# Brain_V0_1.net
KiCad netlist of a schematic drawn in EAGLE
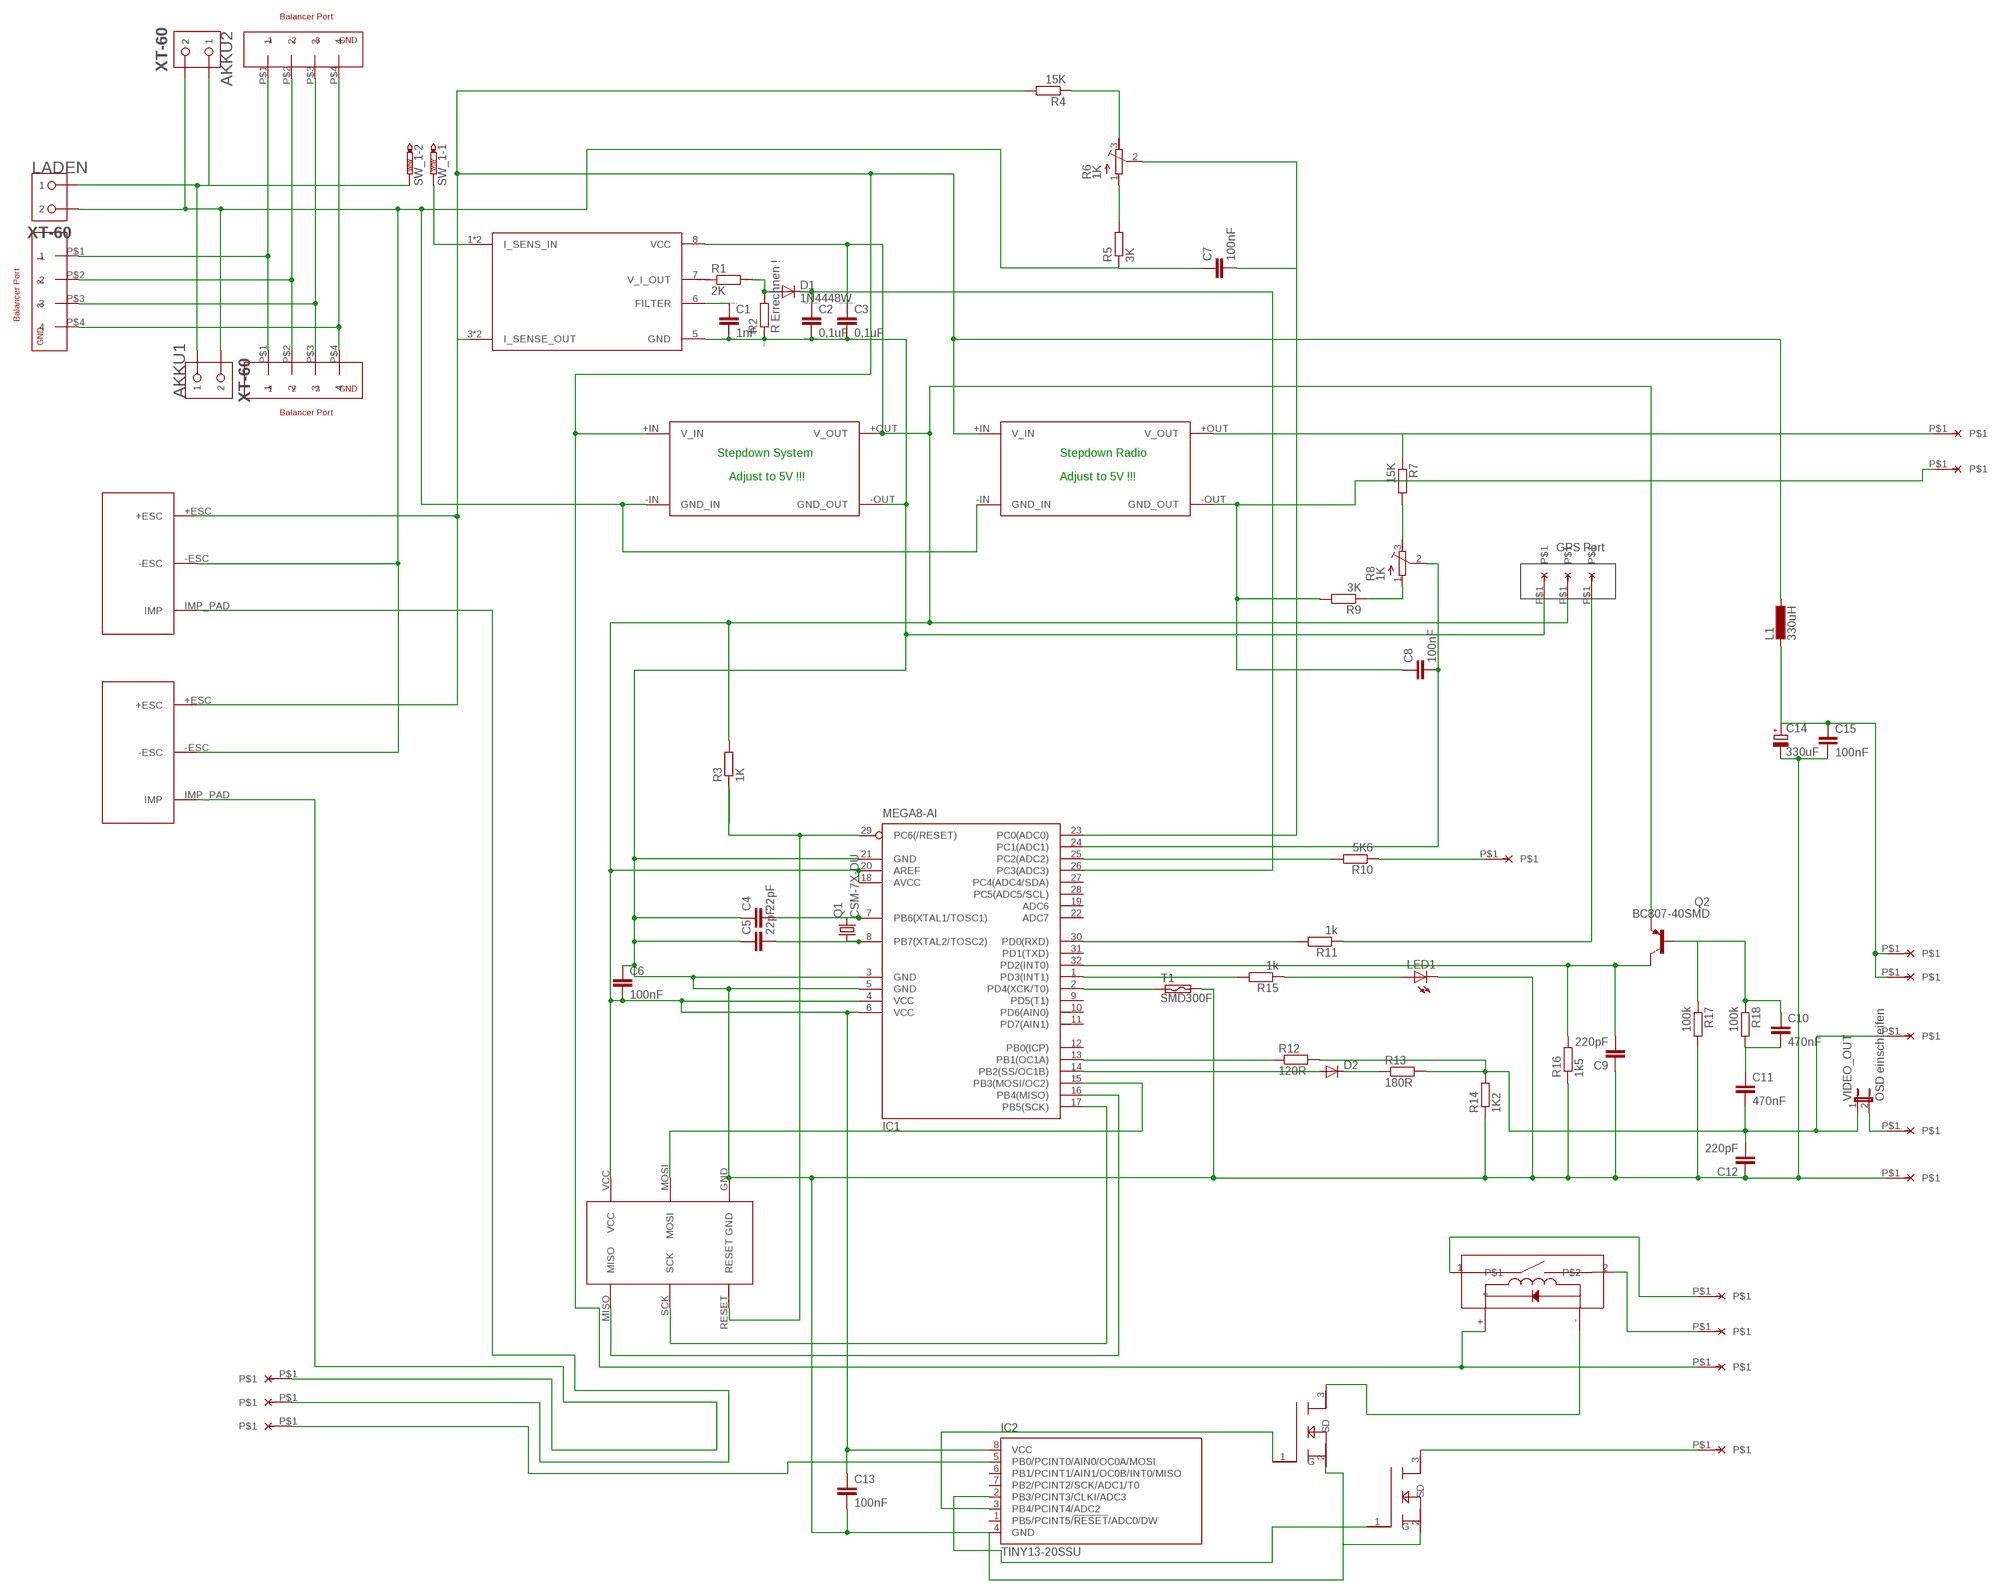
[diagram p0: schematic, sheet 1]

(export (version "E")
  (design (tool "Eeschema 10.0.6"))
  (components
    (comp (ref "5V_GPS")
      (value "LöTPAD_KLEIN")
      (footprint "eagle-import:LöTPAD_KLEIN")
      (libsource (lib "eagle-import") (part "LöTPAD_KLEIN"))
    )
    (comp (ref "AKKU1")
      (value "XT-60")
      (footprint "eagle-import:XT-60")
      (libsource (lib "eagle-import") (part "XT-60"))
    )
    (comp (ref "AKKU2")
      (value "XT-60")
      (footprint "eagle-import:XT-60")
      (libsource (lib "eagle-import") (part "XT-60"))
    )
    (comp (ref "BALANCER_1")
      (value "BALANCER_3S")
      (footprint "eagle-import:BALANCER_3S")
      (libsource (lib "eagle-import") (part "BALANCER_3S"))
    )
    (comp (ref "BALANCER_2")
      (value "BALANCER_3S")
      (footprint "eagle-import:BALANCER_3S")
      (libsource (lib "eagle-import") (part "BALANCER_3S"))
    )
    (comp (ref "BALANCE_OUT")
      (value "BALANCER_3S")
      (footprint "eagle-import:BALANCER_3S")
      (libsource (lib "eagle-import") (part "BALANCER_3S"))
    )
    (comp (ref "BEC+")
      (value "LöTPAD_KLEIN")
      (footprint "eagle-import:LöTPAD_KLEIN")
      (libsource (lib "eagle-import") (part "LöTPAD_KLEIN"))
    )
    (comp (ref "BEC-")
      (value "LöTPAD_KLEIN")
      (footprint "eagle-import:LöTPAD_KLEIN")
      (libsource (lib "eagle-import") (part "LöTPAD_KLEIN"))
    )
    (comp (ref "C1")
      (value "1nF")
      (footprint "eagle-import:C0603K")
      (libsource (lib "eagle-import") (part "resistor_C-EUC0603K"))
    )
    (comp (ref "C2")
      (value "0,1uF")
      (footprint "eagle-import:C0603K")
      (libsource (lib "eagle-import") (part "resistor_C-EUC0603K"))
    )
    (comp (ref "C3")
      (value "0,1uF")
      (footprint "eagle-import:C0603K")
      (libsource (lib "eagle-import") (part "resistor_C-EUC0603K"))
    )
    (comp (ref "C4")
      (value "22pF")
      (footprint "eagle-import:C0603K")
      (libsource (lib "eagle-import") (part "C-EUC0603K"))
    )
    (comp (ref "C5")
      (value "22pF")
      (footprint "eagle-import:C0603K")
      (libsource (lib "eagle-import") (part "C-EUC0603K"))
    )
    (comp (ref "C6")
      (value "100nF")
      (footprint "eagle-import:C0603K")
      (libsource (lib "eagle-import") (part "C-EUC0603K"))
    )
    (comp (ref "C7")
      (value "100nF")
      (footprint "eagle-import:C0603K")
      (libsource (lib "eagle-import") (part "C-EUC0603K"))
    )
    (comp (ref "C8")
      (value "100nF")
      (footprint "eagle-import:C0603K")
      (libsource (lib "eagle-import") (part "C-EUC0603K"))
    )
    (comp (ref "C9")
      (value "220pF")
      (footprint "eagle-import:C0603K")
      (libsource (lib "eagle-import") (part "C-EUC0603K"))
    )
    (comp (ref "C10")
      (value "470nF")
      (footprint "eagle-import:C1206")
      (libsource (lib "eagle-import") (part "C-EUC1206"))
    )
    (comp (ref "C11")
      (value "470nF")
      (footprint "eagle-import:C1206")
      (libsource (lib "eagle-import") (part "C-EUC1206"))
    )
    (comp (ref "C12")
      (value "220pF")
      (footprint "eagle-import:C0603K")
      (libsource (lib "eagle-import") (part "C-EUC0603K"))
    )
    (comp (ref "C13")
      (value "100nF")
      (footprint "eagle-import:C0603K")
      (libsource (lib "eagle-import") (part "C-EUC0603K"))
    )
    (comp (ref "C14")
      (value "330uF")
      (footprint "eagle-import:153CLV-0807")
      (libsource (lib "eagle-import") (part "CPOL-EU153CLV-0807"))
    )
    (comp (ref "C15")
      (value "100nF")
      (footprint "eagle-import:C0603K")
      (libsource (lib "eagle-import") (part "C-EUC0603K"))
    )
    (comp (ref "CAMERA_VIDEO")
      (value "LöTPAD_KLEIN")
      (footprint "eagle-import:LöTPAD_KLEIN")
      (libsource (lib "eagle-import") (part "LöTPAD_KLEIN"))
    )
    (comp (ref "CH1_IN")
      (value "LöTPAD_KLEIN")
      (footprint "eagle-import:LöTPAD_KLEIN")
      (libsource (lib "eagle-import") (part "LöTPAD_KLEIN"))
    )
    (comp (ref "CH2_IN")
      (value "LöTPAD_KLEIN")
      (footprint "eagle-import:LöTPAD_KLEIN")
      (libsource (lib "eagle-import") (part "LöTPAD_KLEIN"))
    )
    (comp (ref "CH3_IN")
      (value "LöTPAD_KLEIN")
      (footprint "eagle-import:LöTPAD_KLEIN")
      (libsource (lib "eagle-import") (part "LöTPAD_KLEIN"))
    )
    (comp (ref "D1")
      (value "1N4448W")
      (footprint "eagle-import:SOD523")
      (libsource (lib "eagle-import") (part "DIODE-SOD523"))
    )
    (comp (ref "D2")
      (value "DIODE-DO-214AC")
      (footprint "eagle-import:DO-214AC")
      (libsource (lib "eagle-import") (part "DIODE-DO-214AC"))
    )
    (comp (ref "ESC1")
      (value "MOT_CONNECTOR")
      (footprint "eagle-import:MOT_CONNECTOR")
      (libsource (lib "eagle-import") (part "MOT_CONNECTOR"))
    )
    (comp (ref "ESC2")
      (value "MOT_CONNECTOR")
      (footprint "eagle-import:MOT_CONNECTOR")
      (libsource (lib "eagle-import") (part "MOT_CONNECTOR"))
    )
    (comp (ref "FILTER")
      (value "LöTPAD_KLEIN")
      (footprint "eagle-import:LöTPAD_KLEIN")
      (libsource (lib "eagle-import") (part "LöTPAD_KLEIN"))
    )
    (comp (ref "FILTER_")
      (value "LöTPAD_KLEIN")
      (footprint "eagle-import:LöTPAD_KLEIN")
      (libsource (lib "eagle-import") (part "LöTPAD_KLEIN"))
    )
    (comp (ref "GND_GPS")
      (value "LöTPAD_KLEIN")
      (footprint "eagle-import:LöTPAD_KLEIN")
      (libsource (lib "eagle-import") (part "LöTPAD_KLEIN"))
    )
    (comp (ref "GND_VIDEO")
      (value "LöTPAD_KLEIN")
      (footprint "eagle-import:LöTPAD_KLEIN")
      (libsource (lib "eagle-import") (part "LöTPAD_KLEIN"))
    )
    (comp (ref "IC1")
      (value "MEGA8-AI")
      (footprint "eagle-import:TQFP32-08")
      (fields (field (name "MPN") "ATMEGA8-16AU"))
      (libsource (lib "eagle-import") (part "MEGA8-AI"))
    )
    (comp (ref "IC2")
      (value "TINY13-20SSU")
      (footprint "eagle-import:8S1")
      (fields (field (name "MPN") "ATTINY13-20SSU"))
      (libsource (lib "eagle-import") (part "TINY13SSU-20"))
    )
    (comp (ref "IR_GND")
      (value "LöTPAD_KLEIN")
      (footprint "eagle-import:LöTPAD_KLEIN")
      (libsource (lib "eagle-import") (part "LöTPAD_KLEIN"))
    )
    (comp (ref "IR_VCC")
      (value "LöTPAD_KLEIN")
      (footprint "eagle-import:LöTPAD_KLEIN")
      (libsource (lib "eagle-import") (part "LöTPAD_KLEIN"))
    )
    (comp (ref "L1")
      (value "330uH")
      (footprint "eagle-import:POWER-CHOKE_WE-TPC")
      (libsource (lib "eagle-import") (part "L-EUWE-TPC"))
    )
    (comp (ref "LADEN")
      (value "XT-60")
      (footprint "eagle-import:XT-60")
      (libsource (lib "eagle-import") (part "XT-60"))
    )
    (comp (ref "LED1")
      (value "LEDCHIP-LED0603")
      (footprint "eagle-import:CHIP-LED0603")
      (libsource (lib "eagle-import") (part "LEDCHIP-LED0603"))
    )
    (comp (ref "Q1")
      (value "CSM-7X-DU")
      (footprint "eagle-import:CSM-7X-DU")
      (libsource (lib "eagle-import") (part "CSM-7X-DU"))
    )
    (comp (ref "Q2")
      (value "BC807-40SMD")
      (footprint "eagle-import:SOT23-BEC")
      (libsource (lib "eagle-import") (part "BC807SMD-40"))
    )
    (comp (ref "R1")
      (value "2K")
      (footprint "eagle-import:R0603")
      (libsource (lib "eagle-import") (part "resistor_R-EU_R0603"))
    )
    (comp (ref "R2")
      (value "R Errechnen !")
      (footprint "eagle-import:R0603")
      (libsource (lib "eagle-import") (part "resistor_R-EU_R0603"))
    )
    (comp (ref "R3")
      (value "1K")
      (footprint "eagle-import:R0603")
      (libsource (lib "eagle-import") (part "R-EU_R0603"))
    )
    (comp (ref "R4")
      (value "15K")
      (footprint "eagle-import:R0603")
      (libsource (lib "eagle-import") (part "R-EU_R0603"))
    )
    (comp (ref "R5")
      (value "3K")
      (footprint "eagle-import:R0603")
      (libsource (lib "eagle-import") (part "R-EU_R0603"))
    )
    (comp (ref "R6")
      (value "1K")
      (footprint "eagle-import:RTRIM3103")
      (libsource (lib "eagle-import") (part "R-TRIMM3103"))
    )
    (comp (ref "R7")
      (value "15K")
      (footprint "eagle-import:R0603")
      (libsource (lib "eagle-import") (part "R-EU_R0603"))
    )
    (comp (ref "R8")
      (value "1K")
      (footprint "eagle-import:RTRIM3103")
      (libsource (lib "eagle-import") (part "R-TRIMM3103"))
    )
    (comp (ref "R9")
      (value "3K")
      (footprint "eagle-import:R0603")
      (libsource (lib "eagle-import") (part "R-EU_R0603"))
    )
    (comp (ref "R10")
      (value "5K6")
      (footprint "eagle-import:R0603")
      (libsource (lib "eagle-import") (part "R-EU_R0603"))
    )
    (comp (ref "R11")
      (value "1k")
      (footprint "eagle-import:R0603")
      (libsource (lib "eagle-import") (part "R-EU_R0603"))
    )
    (comp (ref "R12")
      (value "120R")
      (footprint "eagle-import:R0603")
      (libsource (lib "eagle-import") (part "R-EU_R0603"))
    )
    (comp (ref "R13")
      (value "180R")
      (footprint "eagle-import:R0603")
      (libsource (lib "eagle-import") (part "R-EU_R0603"))
    )
    (comp (ref "R14")
      (value "1K2")
      (footprint "eagle-import:R0603")
      (libsource (lib "eagle-import") (part "R-EU_R0603"))
    )
    (comp (ref "R15")
      (value "1k")
      (footprint "eagle-import:R0603")
      (libsource (lib "eagle-import") (part "R-EU_R0603"))
    )
    (comp (ref "R16")
      (value "1k5")
      (footprint "eagle-import:R0603")
      (libsource (lib "eagle-import") (part "R-EU_R0603"))
    )
    (comp (ref "R17")
      (value "100k")
      (footprint "eagle-import:R0603")
      (libsource (lib "eagle-import") (part "R-EU_R0603"))
    )
    (comp (ref "R18")
      (value "100k")
      (footprint "eagle-import:R0603")
      (libsource (lib "eagle-import") (part "R-EU_R0603"))
    )
    (comp (ref "RSSI_IN")
      (value "LöTPAD_KLEIN")
      (footprint "eagle-import:LöTPAD_KLEIN")
      (libsource (lib "eagle-import") (part "LöTPAD_KLEIN"))
    )
    (comp (ref "RX_GPS")
      (value "LöTPAD_KLEIN")
      (footprint "eagle-import:LöTPAD_KLEIN")
      (libsource (lib "eagle-import") (part "LöTPAD_KLEIN"))
    )
    (comp (ref "STEPDOWN_RADIO")
      (value "STEPDOWN_MINI")
      (footprint "eagle-import:STEPDOWN_SMALL")
      (libsource (lib "eagle-import") (part "STEPDOWN_MINI"))
    )
    (comp (ref "STEPDOWN_SYSTEM")
      (value "STEPDOWN_MINI")
      (footprint "eagle-import:STEPDOWN_SMALL")
      (libsource (lib "eagle-import") (part "STEPDOWN_MINI"))
    )
    (comp (ref "SW_1")
      (value "PTR2")
      (footprint "eagle-import:P2-38-17")
      (libsource (lib "eagle-import") (part "PTR2"))
    )
    (comp (ref "T1")
      (value "SMD300F")
      (footprint "eagle-import:SMD050F")
      (libsource (lib "eagle-import") (part "SMDF300"))
    )
    (comp (ref "U$1")
      (value "REED-RELAIS")
      (footprint "eagle-import:REED-RELAIS")
      (libsource (lib "eagle-import") (part "REED-RELAIS"))
    )
    (comp (ref "U$2")
      (value "IRLM2502")
      (footprint "eagle-import:SOT23")
      (libsource (lib "eagle-import") (part "IRLM2502"))
    )
    (comp (ref "U$3")
      (value "I_SENSE_IC")
      (footprint "eagle-import:SOIC8")
      (libsource (lib "eagle-import") (part "I_SENSE_IC"))
    )
    (comp (ref "U$4")
      (value "ICSP_6P")
      (footprint "eagle-import:ICSP_6P")
      (libsource (lib "eagle-import") (part "ICSP_6P"))
    )
    (comp (ref "U$5")
      (value "IRLM2502")
      (footprint "eagle-import:SOT23")
      (libsource (lib "eagle-import") (part "IRLM2502"))
    )
    (comp (ref "VCC_CAM")
      (value "LöTPAD_KLEIN")
      (footprint "eagle-import:LöTPAD_KLEIN")
      (libsource (lib "eagle-import") (part "LöTPAD_KLEIN"))
    )
    (comp (ref "VCC_VTX")
      (value "LöTPAD_KLEIN")
      (footprint "eagle-import:LöTPAD_KLEIN")
      (libsource (lib "eagle-import") (part "LöTPAD_KLEIN"))
    )
    (comp (ref "VIDEO")
      (value "LöTPAD_KLEIN")
      (footprint "eagle-import:LöTPAD_KLEIN")
      (libsource (lib "eagle-import") (part "LöTPAD_KLEIN"))
    )
    (comp (ref "VIDEO_OUT")
      (value "OSD einschleifen")
      (footprint "eagle-import:JP1")
      (libsource (lib "eagle-import") (part "JP1E"))
    )
  )
  (nets
    (net (code "1") (name "Net-(AKKU1-1)") (class "Default")
      (node (ref "AKKU1") (pin "BATT") (pinfunction "1_BATT") (pintype "passive"))
      (node (ref "AKKU2") (pin "BATT") (pinfunction "1_BATT") (pintype "passive"))
      (node (ref "LADEN") (pin "BATT") (pinfunction "1_BATT") (pintype "passive"))
      (node (ref "SW_1") (pin "TP-2") (pinfunction "TP_TP-2") (pintype "input"))
    )
    (net (code "2") (name "Net-(AKKU1-2)") (class "Default")
      (node (ref "AKKU1") (pin "GND") (pinfunction "2_GND") (pintype "passive"))
      (node (ref "AKKU2") (pin "GND") (pinfunction "2_GND") (pintype "passive"))
      (node (ref "C7") (pin "1") (pinfunction "1_1") (pintype "passive"))
      (node (ref "ESC1") (pin "-ESC") (pinfunction "-ESC_-ESC") (pintype "bidirectional"))
      (node (ref "ESC2") (pin "-ESC") (pinfunction "-ESC_-ESC") (pintype "bidirectional"))
      (node (ref "LADEN") (pin "GND") (pinfunction "2_GND") (pintype "passive"))
      (node (ref "R5") (pin "1") (pinfunction "1_1") (pintype "passive"))
      (node (ref "STEPDOWN_RADIO") (pin "-IN") (pinfunction "GND_IN_-IN") (pintype "input"))
      (node (ref "STEPDOWN_SYSTEM") (pin "-IN") (pinfunction "GND_IN_-IN") (pintype "input"))
    )
    (net (code "3") (name "Net-(BALANCER_1-1)") (class "Default")
      (node (ref "BALANCER_1") (pin "P$1") (pinfunction "1_P$1") (pintype "bidirectional"))
      (node (ref "BALANCER_2") (pin "P$1") (pinfunction "1_P$1") (pintype "bidirectional"))
      (node (ref "BALANCE_OUT") (pin "P$1") (pinfunction "1_P$1") (pintype "bidirectional"))
    )
    (net (code "4") (name "Net-(BALANCER_1-2)") (class "Default")
      (node (ref "BALANCER_1") (pin "P$2") (pinfunction "2_P$2") (pintype "bidirectional"))
      (node (ref "BALANCER_2") (pin "P$2") (pinfunction "2_P$2") (pintype "bidirectional"))
      (node (ref "BALANCE_OUT") (pin "P$2") (pinfunction "2_P$2") (pintype "bidirectional"))
    )
    (net (code "5") (name "Net-(BALANCER_1-3)") (class "Default")
      (node (ref "BALANCER_1") (pin "P$3") (pinfunction "3_P$3") (pintype "bidirectional"))
      (node (ref "BALANCER_2") (pin "P$3") (pinfunction "3_P$3") (pintype "bidirectional"))
      (node (ref "BALANCE_OUT") (pin "P$3") (pinfunction "3_P$3") (pintype "bidirectional"))
    )
    (net (code "6") (name "Net-(BALANCER_1-4)") (class "Default")
      (node (ref "BALANCER_1") (pin "P$4") (pinfunction "4_P$4") (pintype "bidirectional"))
      (node (ref "BALANCER_2") (pin "P$4") (pinfunction "4_P$4") (pintype "bidirectional"))
      (node (ref "BALANCE_OUT") (pin "P$4") (pinfunction "4_P$4") (pintype "bidirectional"))
    )
    (net (code "7") (name "Net-(C10-Pad1)") (class "Default")
      (node (ref "C10") (pin "1") (pinfunction "1_1") (pintype "passive"))
      (node (ref "Q2") (pin "B") (pinfunction "B_B") (pintype "passive"))
      (node (ref "R17") (pin "1") (pinfunction "1_1") (pintype "passive"))
      (node (ref "R18") (pin "1") (pinfunction "1_1") (pintype "passive"))
    )
    (net (code "8") (name "Net-(C10-Pad2)") (class "Default")
      (node (ref "C10") (pin "2") (pinfunction "2_2") (pintype "passive"))
      (node (ref "C11") (pin "1") (pinfunction "1_1") (pintype "passive"))
      (node (ref "R18") (pin "2") (pinfunction "2_2") (pintype "passive"))
    )
    (net (code "9") (name "Net-(C11-Pad2)") (class "Default")
      (node (ref "C11") (pin "2") (pinfunction "2_2") (pintype "passive"))
      (node (ref "C12") (pin "2") (pinfunction "2_2") (pintype "passive"))
      (node (ref "CAMERA_VIDEO") (pin "P$1") (pinfunction "P$1_P$1") (pintype "bidirectional"))
      (node (ref "R12") (pin "2") (pinfunction "2_2") (pintype "passive"))
      (node (ref "R13") (pin "2") (pinfunction "2_2") (pintype "passive"))
      (node (ref "R14") (pin "2") (pinfunction "2_2") (pintype "passive"))
      (node (ref "VIDEO_OUT") (pin "1") (pinfunction "1_1") (pintype "passive"))
    )
    (net (code "10") (name "Net-(C14-Pad+)") (class "Default")
      (node (ref "C14") (pin "+") (pinfunction "+_+") (pintype "passive"))
      (node (ref "C15") (pin "1") (pinfunction "1_1") (pintype "passive"))
      (node (ref "L1") (pin "2") (pinfunction "2_2") (pintype "passive"))
      (node (ref "VCC_CAM") (pin "P$1") (pinfunction "P$1_P$1") (pintype "bidirectional"))
      (node (ref "VCC_VTX") (pin "P$1") (pinfunction "P$1_P$1") (pintype "bidirectional"))
    )
    (net (code "11") (name "Net-(D1-PadA)") (class "Default")
      (node (ref "D1") (pin "A") (pinfunction "A_A") (pintype "passive"))
      (node (ref "R1") (pin "2") (pinfunction "2_2") (pintype "passive"))
      (node (ref "R2") (pin "2") (pinfunction "2_2") (pintype "passive"))
    )
    (net (code "12") (name "Net-(D2-PadC)") (class "Default")
      (node (ref "D2") (pin "C") (pinfunction "C_C") (pintype "passive"))
      (node (ref "R13") (pin "1") (pinfunction "1_1") (pintype "passive"))
    )
    (net (code "13") (name "Net-(ESC1-IMP)") (class "Default")
      (node (ref "CH2_IN") (pin "P$1") (pinfunction "P$1_P$1") (pintype "bidirectional"))
      (node (ref "ESC1") (pin "IMP_PAD") (pinfunction "IMP_IMP_PAD") (pintype "bidirectional"))
    )
    (net (code "14") (name "Net-(ESC2-IMP)") (class "Default")
      (node (ref "CH1_IN") (pin "P$1") (pinfunction "P$1_P$1") (pintype "bidirectional"))
      (node (ref "ESC2") (pin "IMP_PAD") (pinfunction "IMP_IMP_PAD") (pintype "bidirectional"))
    )
    (net (code "15") (name "Net-(IC1-AREF)") (class "Default")
      (node (ref "5V_GPS") (pin "P$1") (pinfunction "P$1_P$1") (pintype "bidirectional"))
      (node (ref "C13") (pin "1") (pinfunction "1_1") (pintype "passive"))
      (node (ref "C3") (pin "1") (pinfunction "1_1") (pintype "passive"))
      (node (ref "C6") (pin "2") (pinfunction "2_2") (pintype "passive"))
      (node (ref "IC1") (pin "18") (pinfunction "AVCC_18") (pintype "power_in"))
      (node (ref "IC1") (pin "20") (pinfunction "AREF_20") (pintype "passive"))
      (node (ref "IC1") (pin "4") (pinfunction "VCC_4") (pintype "power_in"))
      (node (ref "IC1") (pin "6") (pinfunction "VCC_6") (pintype "power_in"))
      (node (ref "IC2") (pin "8") (pinfunction "VCC_8") (pintype "power_in"))
      (node (ref "Q2") (pin "E") (pinfunction "E_E") (pintype "passive"))
      (node (ref "R3") (pin "2") (pinfunction "2_2") (pintype "passive"))
      (node (ref "STEPDOWN_SYSTEM") (pin "+OUT") (pinfunction "V_OUT_+OUT") (pintype "output"))
      (node (ref "U$3") (pin "8") (pinfunction "VCC_8") (pintype "power_in"))
      (node (ref "U$4") (pin "VCC") (pinfunction "VCC_VCC") (pintype "bidirectional"))
    )
    (net (code "16") (name "Net-(IC1-PB1(OC1A))") (class "Default")
      (node (ref "IC1") (pin "13") (pinfunction "PB1(OC1A)_13") (pintype "bidirectional"))
      (node (ref "R12") (pin "1") (pinfunction "1_1") (pintype "passive"))
    )
    (net (code "17") (name "Net-(IC1-PB2(SS{slash}OC1B))") (class "Default")
      (node (ref "D2") (pin "A") (pinfunction "A_A") (pintype "passive"))
      (node (ref "IC1") (pin "14") (pinfunction "PB2(SS/OC1B)_14") (pintype "bidirectional"))
    )
    (net (code "18") (name "Net-(IC1-PB3(MOSI{slash}OC2))") (class "Default")
      (node (ref "IC1") (pin "15") (pinfunction "PB3(MOSI/OC2)_15") (pintype "bidirectional"))
      (node (ref "U$4") (pin "MOSI") (pinfunction "MOSI_MOSI") (pintype "bidirectional"))
    )
    (net (code "19") (name "Net-(IC1-PB4(MISO))") (class "Default")
      (node (ref "IC1") (pin "16") (pinfunction "PB4(MISO)_16") (pintype "bidirectional"))
      (node (ref "U$4") (pin "MISO") (pinfunction "MISO_MISO") (pintype "bidirectional"))
    )
    (net (code "20") (name "Net-(IC1-PB5(SCK))") (class "Default")
      (node (ref "IC1") (pin "17") (pinfunction "PB5(SCK)_17") (pintype "bidirectional"))
      (node (ref "U$4") (pin "SCK") (pinfunction "SCK_SCK") (pintype "bidirectional"))
    )
    (net (code "21") (name "Net-(IC1-PB6(XTAL1{slash}TOSC1))") (class "Default")
      (node (ref "C4") (pin "2") (pinfunction "2_2") (pintype "passive"))
      (node (ref "IC1") (pin "7") (pinfunction "PB6(XTAL1/TOSC1)_7") (pintype "bidirectional"))
      (node (ref "Q1") (pin "2") (pinfunction "2_2") (pintype "passive"))
    )
    (net (code "22") (name "Net-(IC1-PB7(XTAL2{slash}TOSC2))") (class "Default")
      (node (ref "C5") (pin "2") (pinfunction "2_2") (pintype "passive"))
      (node (ref "IC1") (pin "8") (pinfunction "PB7(XTAL2/TOSC2)_8") (pintype "bidirectional"))
      (node (ref "Q1") (pin "1") (pinfunction "1_1") (pintype "passive"))
    )
    (net (code "23") (name "Net-(IC1-PC0(ADC0))") (class "Default")
      (node (ref "C7") (pin "2") (pinfunction "2_2") (pintype "passive"))
      (node (ref "IC1") (pin "23") (pinfunction "PC0(ADC0)_23") (pintype "bidirectional"))
      (node (ref "R6") (pin "2") (pinfunction "S_2") (pintype "passive"))
    )
    (net (code "24") (name "Net-(IC1-PC1(ADC1))") (class "Default")
      (node (ref "C8") (pin "2") (pinfunction "2_2") (pintype "passive"))
      (node (ref "IC1") (pin "24") (pinfunction "PC1(ADC1)_24") (pintype "bidirectional"))
      (node (ref "R8") (pin "2") (pinfunction "S_2") (pintype "passive"))
    )
    (net (code "25") (name "Net-(IC1-PC2(ADC2))") (class "Default")
      (node (ref "IC1") (pin "25") (pinfunction "PC2(ADC2)_25") (pintype "bidirectional"))
      (node (ref "R10") (pin "2") (pinfunction "2_2") (pintype "passive"))
    )
    (net (code "26") (name "Net-(IC1-PC3(ADC3))") (class "Default")
      (node (ref "C2") (pin "1") (pinfunction "1_1") (pintype "passive"))
      (node (ref "D1") (pin "C") (pinfunction "C_C") (pintype "passive"))
      (node (ref "IC1") (pin "26") (pinfunction "PC3(ADC3)_26") (pintype "bidirectional"))
    )
    (net (code "27") (name "Net-(IC1-PC6({slash}RESET))") (class "Default")
      (node (ref "IC1") (pin "29") (pinfunction "PC6(/RESET)_29") (pintype "bidirectional"))
      (node (ref "R3") (pin "1") (pinfunction "1_1") (pintype "passive"))
      (node (ref "U$4") (pin "RESET") (pinfunction "RESET_RESET") (pintype "bidirectional"))
    )
    (net (code "28") (name "Net-(IC1-PD0(RXD))") (class "Default")
      (node (ref "IC1") (pin "30") (pinfunction "PD0(RXD)_30") (pintype "bidirectional"))
      (node (ref "R11") (pin "2") (pinfunction "2_2") (pintype "passive"))
    )
    (net (code "29") (name "Net-(IC1-PD2(INT0))") (class "Default")
      (node (ref "C9") (pin "2") (pinfunction "2_2") (pintype "passive"))
      (node (ref "IC1") (pin "32") (pinfunction "PD2(INT0)_32") (pintype "bidirectional"))
      (node (ref "Q2") (pin "C") (pinfunction "C_C") (pintype "passive"))
      (node (ref "R16") (pin "2") (pinfunction "2_2") (pintype "passive"))
    )
    (net (code "30") (name "Net-(IC1-PD3(INT1))") (class "Default")
      (node (ref "IC1") (pin "1") (pinfunction "PD3(INT1)_1") (pintype "bidirectional"))
      (node (ref "R15") (pin "2") (pinfunction "2_2") (pintype "passive"))
    )
    (net (code "31") (name "Net-(IC1-PD4(XCK{slash}T0))") (class "Default")
      (node (ref "IC1") (pin "2") (pinfunction "PD4(XCK/T0)_2") (pintype "bidirectional"))
      (node (ref "T1") (pin "1") (pinfunction "1_1") (pintype "passive"))
    )
    (net (code "32") (name "Net-(IC2-GND)") (class "Default")
      (node (ref "C1") (pin "2") (pinfunction "2_2") (pintype "passive"))
      (node (ref "C12") (pin "1") (pinfunction "1_1") (pintype "passive"))
      (node (ref "C13") (pin "2") (pinfunction "2_2") (pintype "passive"))
      (node (ref "C14") (pin "-") (pinfunction "-_-") (pintype "passive"))
      (node (ref "C15") (pin "2") (pinfunction "2_2") (pintype "passive"))
      (node (ref "C2") (pin "2") (pinfunction "2_2") (pintype "passive"))
      (node (ref "C3") (pin "2") (pinfunction "2_2") (pintype "passive"))
      (node (ref "C4") (pin "1") (pinfunction "1_1") (pintype "passive"))
      (node (ref "C5") (pin "1") (pinfunction "1_1") (pintype "passive"))
      (node (ref "C6") (pin "1") (pinfunction "1_1") (pintype "passive"))
      (node (ref "C9") (pin "1") (pinfunction "1_1") (pintype "passive"))
      (node (ref "GND_GPS") (pin "P$1") (pinfunction "P$1_P$1") (pintype "bidirectional"))
      (node (ref "GND_VIDEO") (pin "P$1") (pinfunction "P$1_P$1") (pintype "bidirectional"))
      (node (ref "IC1") (pin "21") (pinfunction "GND_21") (pintype "power_in"))
      (node (ref "IC1") (pin "3") (pinfunction "GND_3") (pintype "power_in"))
      (node (ref "IC1") (pin "5") (pinfunction "GND_5") (pintype "power_in"))
      (node (ref "IC2") (pin "4") (pinfunction "GND_4") (pintype "power_in"))
      (node (ref "LED1") (pin "C") (pinfunction "C_C") (pintype "passive"))
      (node (ref "R14") (pin "1") (pinfunction "1_1") (pintype "passive"))
      (node (ref "R16") (pin "1") (pinfunction "1_1") (pintype "passive"))
      (node (ref "R17") (pin "2") (pinfunction "2_2") (pintype "passive"))
      (node (ref "R2") (pin "1") (pinfunction "1_1") (pintype "passive"))
      (node (ref "STEPDOWN_SYSTEM") (pin "-OUT") (pinfunction "GND_OUT_-OUT") (pintype "output"))
      (node (ref "T1") (pin "2") (pinfunction "2_2") (pintype "passive"))
      (node (ref "U$2") (pin "2") (pinfunction "S_2") (pintype "bidirectional"))
      (node (ref "U$3") (pin "5") (pinfunction "GND_5") (pintype "power_in"))
      (node (ref "U$4") (pin "GND") (pinfunction "GND_GND") (pintype "bidirectional"))
      (node (ref "U$5") (pin "2") (pinfunction "S_2") (pintype "bidirectional"))
    )
    (net (code "33") (name "Net-(IC2-PB0{slash}PCINT0{slash}AIN0{slash}OC0A{slash}MOSI)") (class "Default")
      (node (ref "CH3_IN") (pin "P$1") (pinfunction "P$1_P$1") (pintype "bidirectional"))
      (node (ref "IC2") (pin "5") (pinfunction "PB0/PCINT0/AIN0/OC0A/MOSI_5") (pintype "bidirectional"))
    )
    (net (code "34") (name "Net-(IC2-PB3{slash}PCINT3{slash}CLKI{slash}ADC3)") (class "Default")
      (node (ref "IC2") (pin "2") (pinfunction "PB3/PCINT3/CLKI/ADC3_2") (pintype "bidirectional"))
      (node (ref "U$5") (pin "1") (pinfunction "G_1") (pintype "bidirectional"))
    )
    (net (code "35") (name "Net-(IC2-PB4{slash}PCINT4{slash}ADC2)") (class "Default")
      (node (ref "IC2") (pin "3") (pinfunction "PB4/PCINT4/ADC2_3") (pintype "bidirectional"))
      (node (ref "U$2") (pin "1") (pinfunction "G_1") (pintype "bidirectional"))
    )
    (net (code "36") (name "Net-(LED1-PadA)") (class "Default")
      (node (ref "LED1") (pin "A") (pinfunction "A_A") (pintype "passive"))
      (node (ref "R15") (pin "1") (pinfunction "1_1") (pintype "passive"))
    )
    (net (code "37") (name "Net-(R6-A)") (class "Default")
      (node (ref "R5") (pin "2") (pinfunction "2_2") (pintype "passive"))
      (node (ref "R6") (pin "1") (pinfunction "A_1") (pintype "passive"))
    )
    (net (code "38") (name "Net-(R6-E)") (class "Default")
      (node (ref "R4") (pin "1") (pinfunction "1_1") (pintype "passive"))
      (node (ref "R6") (pin "3") (pinfunction "E_3") (pintype "passive"))
    )
    (net (code "39") (name "Net-(R8-A)") (class "Default")
      (node (ref "R8") (pin "1") (pinfunction "A_1") (pintype "passive"))
      (node (ref "R9") (pin "1") (pinfunction "1_1") (pintype "passive"))
    )
    (net (code "40") (name "Net-(R8-E)") (class "Default")
      (node (ref "R7") (pin "2") (pinfunction "2_2") (pintype "passive"))
      (node (ref "R8") (pin "3") (pinfunction "E_3") (pintype "passive"))
    )
    (net (code "41") (name "Net-(R10-Pad1)") (class "Default")
      (node (ref "R10") (pin "1") (pinfunction "1_1") (pintype "passive"))
      (node (ref "RSSI_IN") (pin "P$1") (pinfunction "P$1_P$1") (pintype "bidirectional"))
    )
    (net (code "42") (name "Net-(R11-Pad1)") (class "Default")
      (node (ref "R11") (pin "1") (pinfunction "1_1") (pintype "passive"))
      (node (ref "RX_GPS") (pin "P$1") (pinfunction "P$1_P$1") (pintype "bidirectional"))
    )
    (net (code "43") (name "Net-(STEPDOWN_RADIO-GND_OUT)") (class "Default")
      (node (ref "BEC-") (pin "P$1") (pinfunction "P$1_P$1") (pintype "bidirectional"))
      (node (ref "C8") (pin "1") (pinfunction "1_1") (pintype "passive"))
      (node (ref "R9") (pin "2") (pinfunction "2_2") (pintype "passive"))
      (node (ref "STEPDOWN_RADIO") (pin "-OUT") (pinfunction "GND_OUT_-OUT") (pintype "output"))
    )
    (net (code "44") (name "Net-(STEPDOWN_RADIO-V_IN)") (class "Default")
      (node (ref "ESC1") (pin "+ESC") (pinfunction "+ESC_+ESC") (pintype "bidirectional"))
      (node (ref "ESC2") (pin "+ESC") (pinfunction "+ESC_+ESC") (pintype "bidirectional"))
      (node (ref "IR_VCC") (pin "P$1") (pinfunction "P$1_P$1") (pintype "bidirectional"))
      (node (ref "L1") (pin "1") (pinfunction "1_1") (pintype "passive"))
      (node (ref "R4") (pin "2") (pinfunction "2_2") (pintype "passive"))
      (node (ref "STEPDOWN_RADIO") (pin "+IN") (pinfunction "V_IN_+IN") (pintype "input"))
      (node (ref "STEPDOWN_SYSTEM") (pin "+IN") (pinfunction "V_IN_+IN") (pintype "input"))
      (node (ref "U$1") (pin "+") (pinfunction "+_+") (pintype "bidirectional"))
      (node (ref "U$3") (pin "3") (pinfunction "I_SENSE_OUT_3") (pintype "output"))
      (node (ref "U$3") (pin "4") (pinfunction "I_SENSE_OUT_4") (pintype "output"))
    )
    (net (code "45") (name "Net-(STEPDOWN_RADIO-V_OUT)") (class "Default")
      (node (ref "BEC+") (pin "P$1") (pinfunction "P$1_P$1") (pintype "bidirectional"))
      (node (ref "R7") (pin "1") (pinfunction "1_1") (pintype "passive"))
      (node (ref "STEPDOWN_RADIO") (pin "+OUT") (pinfunction "V_OUT_+OUT") (pintype "output"))
    )
    (net (code "46") (name "Net-(SW_1A-TP)") (class "Default")
      (node (ref "SW_1") (pin "TP-1") (pinfunction "TP_TP-1") (pintype "input"))
      (node (ref "U$3") (pin "1") (pinfunction "I_SENS_IN_1") (pintype "input"))
      (node (ref "U$3") (pin "2") (pinfunction "I_SENS_IN_2") (pintype "input"))
    )
    (net (code "47") (name "Net-(U$1-P$1)") (class "Default")
      (node (ref "FILTER") (pin "P$1") (pinfunction "P$1_P$1") (pintype "bidirectional"))
      (node (ref "U$1") (pin "1") (pinfunction "P$1_1") (pintype "bidirectional"))
    )
    (net (code "48") (name "Net-(U$1-P$2)") (class "Default")
      (node (ref "FILTER_") (pin "P$1") (pinfunction "P$1_P$1") (pintype "bidirectional"))
      (node (ref "U$1") (pin "2") (pinfunction "P$2_2") (pintype "bidirectional"))
    )
    (net (code "49") (name "Net-(U$2-D)") (class "Default")
      (node (ref "U$1") (pin "-") (pinfunction "-_-") (pintype "bidirectional"))
      (node (ref "U$2") (pin "3") (pinfunction "D_3") (pintype "bidirectional"))
    )
    (net (code "50") (name "Net-(U$3-FILTER)") (class "Default")
      (node (ref "C1") (pin "1") (pinfunction "1_1") (pintype "passive"))
      (node (ref "U$3") (pin "6") (pinfunction "FILTER_6") (pintype "bidirectional"))
    )
    (net (code "51") (name "Net-(U$3-V_I_OUT)") (class "Default")
      (node (ref "R1") (pin "1") (pinfunction "1_1") (pintype "passive"))
      (node (ref "U$3") (pin "7") (pinfunction "V_I_OUT_7") (pintype "output"))
    )
    (net (code "52") (name "Net-(U$5-D)") (class "Default")
      (node (ref "IR_GND") (pin "P$1") (pinfunction "P$1_P$1") (pintype "bidirectional"))
      (node (ref "U$5") (pin "3") (pinfunction "D_3") (pintype "bidirectional"))
    )
    (net (code "53") (name "Net-(VIDEO-PadP$1)") (class "Default")
      (node (ref "VIDEO") (pin "P$1") (pinfunction "P$1_P$1") (pintype "bidirectional"))
      (node (ref "VIDEO_OUT") (pin "2") (pinfunction "2_2") (pintype "passive"))
    )
    (net (code "54") (name "unconnected-(IC1-ADC6-Pad19)") (class "Default")
      (node (ref "IC1") (pin "19") (pinfunction "ADC6_19") (pintype "bidirectional"))
    )
    (net (code "55") (name "unconnected-(IC1-ADC7-Pad22)") (class "Default")
      (node (ref "IC1") (pin "22") (pinfunction "ADC7_22") (pintype "bidirectional"))
    )
    (net (code "56") (name "unconnected-(IC1-PB0(ICP)-Pad12)") (class "Default")
      (node (ref "IC1") (pin "12") (pinfunction "PB0(ICP)_12") (pintype "bidirectional"))
    )
    (net (code "57") (name "unconnected-(IC1-PC4(ADC4{slash}SDA)-Pad27)") (class "Default")
      (node (ref "IC1") (pin "27") (pinfunction "PC4(ADC4/SDA)_27") (pintype "bidirectional"))
    )
    (net (code "58") (name "unconnected-(IC1-PC5(ADC5{slash}SCL)-Pad28)") (class "Default")
      (node (ref "IC1") (pin "28") (pinfunction "PC5(ADC5/SCL)_28") (pintype "bidirectional"))
    )
    (net (code "59") (name "unconnected-(IC1-PD1(TXD)-Pad31)") (class "Default")
      (node (ref "IC1") (pin "31") (pinfunction "PD1(TXD)_31") (pintype "bidirectional"))
    )
    (net (code "60") (name "unconnected-(IC1-PD5(T1)-Pad9)") (class "Default")
      (node (ref "IC1") (pin "9") (pinfunction "PD5(T1)_9") (pintype "bidirectional"))
    )
    (net (code "61") (name "unconnected-(IC1-PD6(AIN0)-Pad10)") (class "Default")
      (node (ref "IC1") (pin "10") (pinfunction "PD6(AIN0)_10") (pintype "bidirectional"))
    )
    (net (code "62") (name "unconnected-(IC1-PD7(AIN1)-Pad11)") (class "Default")
      (node (ref "IC1") (pin "11") (pinfunction "PD7(AIN1)_11") (pintype "bidirectional"))
    )
    (net (code "63") (name "unconnected-(IC2-PB1{slash}PCINT1{slash}AIN1{slash}OC0B{slash}INT0{slash}MISO-Pad6)") (class "Default")
      (node (ref "IC2") (pin "6") (pinfunction "PB1/PCINT1/AIN1/OC0B/INT0/MISO_6") (pintype "bidirectional"))
    )
    (net (code "64") (name "unconnected-(IC2-PB2{slash}PCINT2{slash}SCK{slash}ADC1{slash}T0-Pad7)") (class "Default")
      (node (ref "IC2") (pin "7") (pinfunction "PB2/PCINT2/SCK/ADC1/T0_7") (pintype "bidirectional"))
    )
    (net (code "65") (name "unconnected-(IC2-PB5{slash}PCINT5{slash}~{RESET}{slash}ADC0{slash}DW-Pad1)") (class "Default")
      (node (ref "IC2") (pin "1") (pinfunction "PB5/PCINT5/~{RESET}/ADC0/DW_1") (pintype "bidirectional"))
    )
  )
)
